# GALX4-0047N_PCB-1109N_REV-A_io_2.net
KiCad netlist of a schematic drawn in Altium Designer
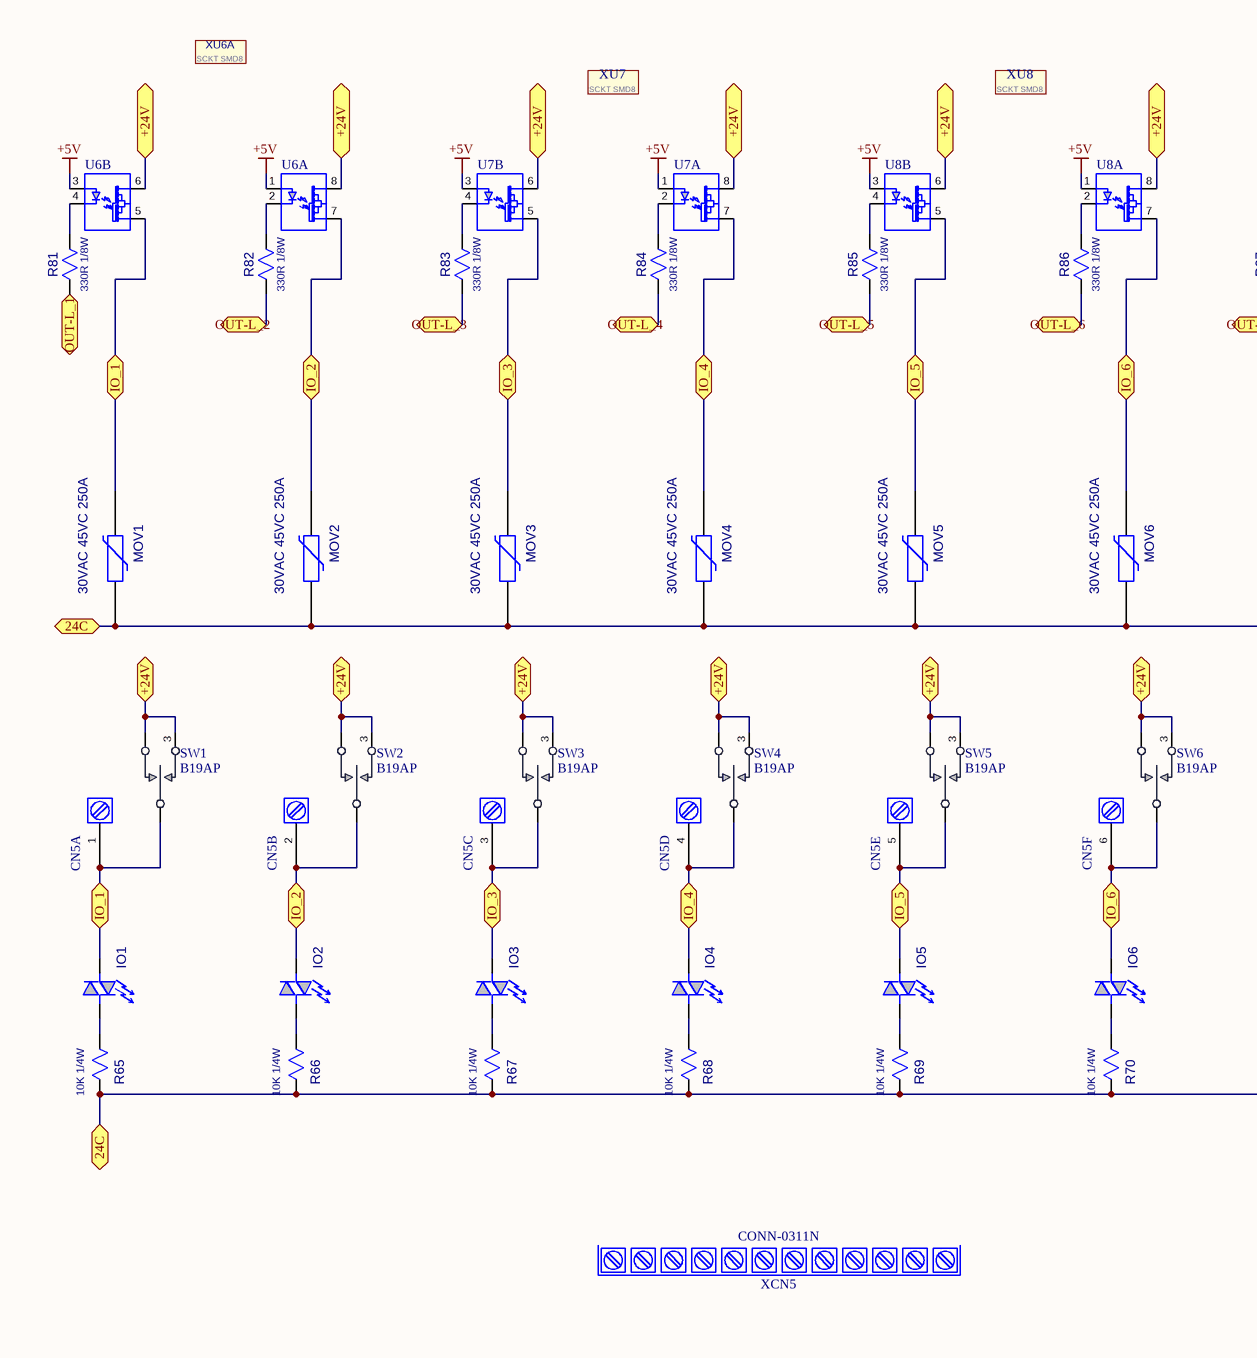
[diagram p0: GALX4-0047N_PCB-1109N_REV-A_io_2.SchDoc, left]
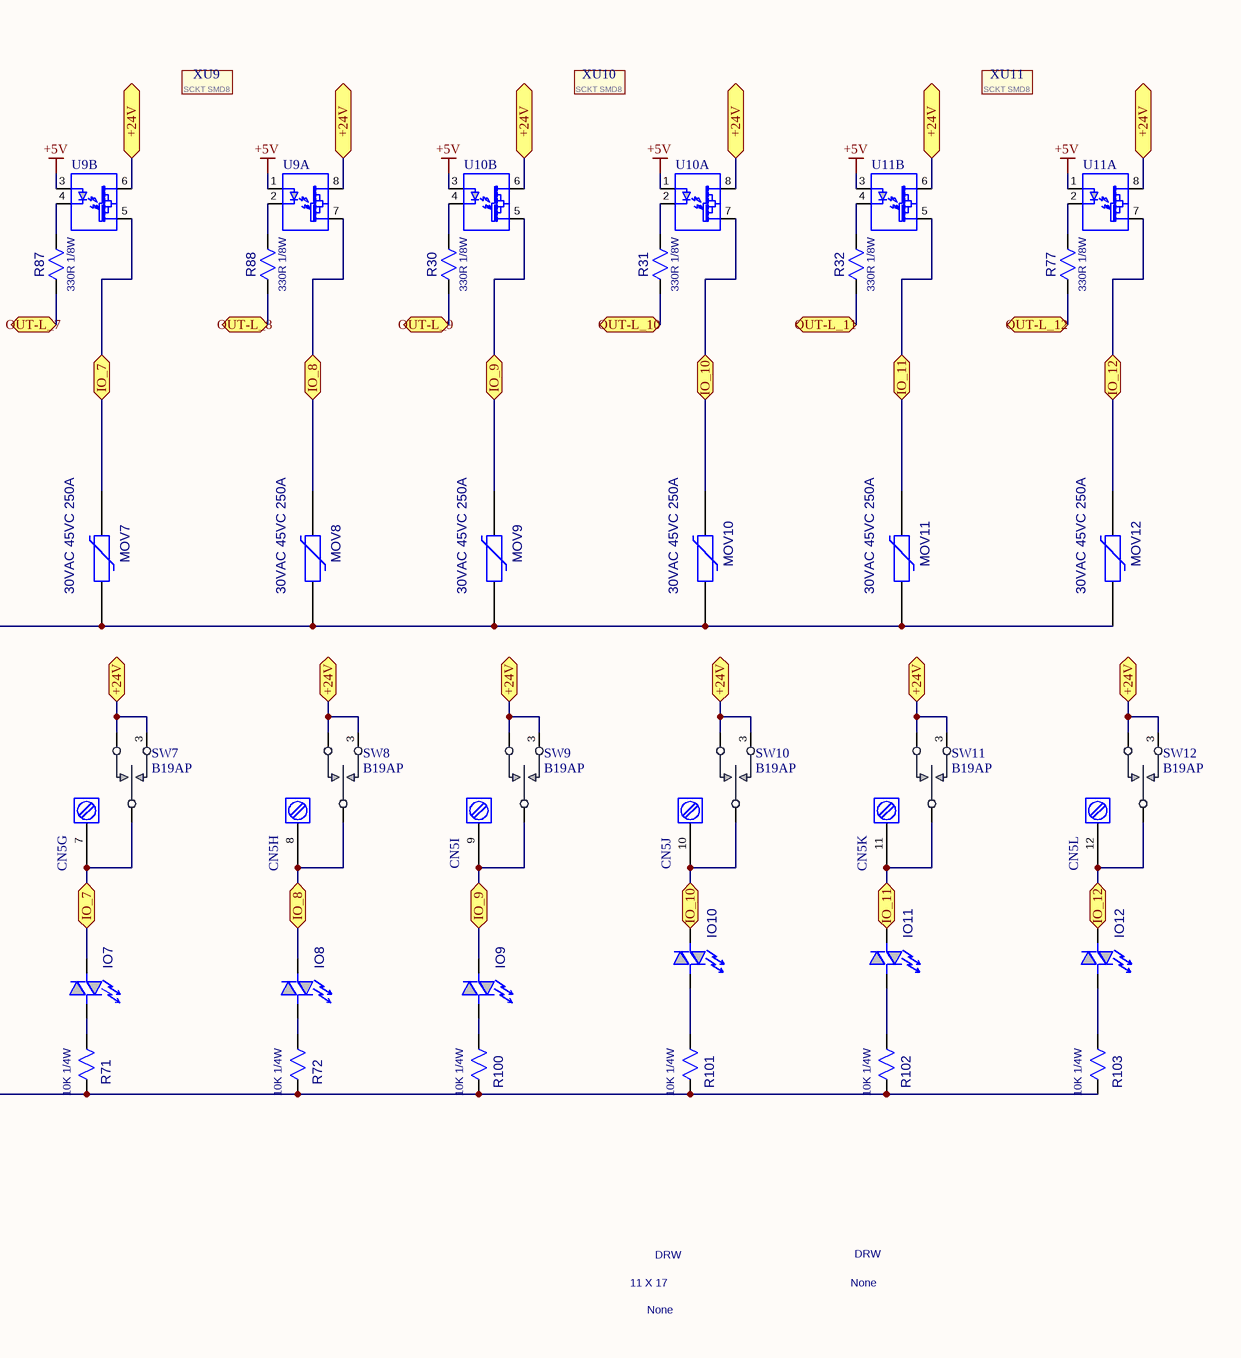
[diagram p1: GALX4-0047N_PCB-1109N_REV-A_io_2.SchDoc, right]

(export (version "E")
  (design (tool "Eeschema 10.0.6"))
  (components
    (comp (ref "CN5")
      (value "CONN-0310N")
      (footprint "CNPIN-5MM-12P-NOSCR")
      (description "CNPIN_5MM_12P")
      (fields (field (name "MANUFACTURER") "PHOENIX"))
      (libsource (lib "") (part "CONN-0310N_1"))
    )
    (comp (ref "IO1")
      (value "LED-0013N")
      (footprint "1206-LED-GREEN")
      (description "LED-1206-BI-G")
      (fields (field (name "MANUFACTURER") "SUNLED"))
      (libsource (lib "SEMICONDUCTOR") (part "LED-0013N"))
    )
    (comp (ref "IO2")
      (value "LED-0013N")
      (footprint "1206-LED-GREEN")
      (description "LED-1206-BI-G")
      (fields (field (name "MANUFACTURER") "SUNLED"))
      (libsource (lib "SEMICONDUCTOR") (part "LED-0013N"))
    )
    (comp (ref "IO3")
      (value "LED-0013N")
      (footprint "1206-LED-GREEN")
      (description "LED-1206-BI-G")
      (fields (field (name "MANUFACTURER") "SUNLED"))
      (libsource (lib "SEMICONDUCTOR") (part "LED-0013N"))
    )
    (comp (ref "IO4")
      (value "LED-0013N")
      (footprint "1206-LED-GREEN")
      (description "LED-1206-BI-G")
      (fields (field (name "MANUFACTURER") "SUNLED"))
      (libsource (lib "SEMICONDUCTOR") (part "LED-0013N"))
    )
    (comp (ref "IO5")
      (value "LED-0013N")
      (footprint "1206-LED-GREEN")
      (description "LED-1206-BI-G")
      (fields (field (name "MANUFACTURER") "SUNLED"))
      (libsource (lib "SEMICONDUCTOR") (part "LED-0013N"))
    )
    (comp (ref "IO6")
      (value "LED-0013N")
      (footprint "1206-LED-GREEN")
      (description "LED-1206-BI-G")
      (fields (field (name "MANUFACTURER") "SUNLED"))
      (libsource (lib "SEMICONDUCTOR") (part "LED-0013N"))
    )
    (comp (ref "IO7")
      (value "LED-0013N")
      (footprint "1206-LED-GREEN")
      (description "LED-1206-BI-G")
      (fields (field (name "MANUFACTURER") "SUNLED"))
      (libsource (lib "SEMICONDUCTOR") (part "LED-0013N"))
    )
    (comp (ref "IO8")
      (value "LED-0013N")
      (footprint "1206-LED-GREEN")
      (description "LED-1206-BI-G")
      (fields (field (name "MANUFACTURER") "SUNLED"))
      (libsource (lib "SEMICONDUCTOR") (part "LED-0013N"))
    )
    (comp (ref "IO9")
      (value "LED-0013N")
      (footprint "1206-LED-GREEN")
      (description "LED-1206-BI-G")
      (fields (field (name "MANUFACTURER") "SUNLED"))
      (libsource (lib "SEMICONDUCTOR") (part "LED-0013N"))
    )
    (comp (ref "IO10")
      (value "LED-0013N")
      (footprint "1206-LED-GREEN")
      (description "LED-1206-BI-G")
      (fields (field (name "MANUFACTURER") "SUNLED"))
      (libsource (lib "SEMICONDUCTOR") (part "LED-0013N"))
    )
    (comp (ref "IO11")
      (value "LED-0013N")
      (footprint "1206-LED-GREEN")
      (description "LED-1206-BI-G")
      (fields (field (name "MANUFACTURER") "SUNLED"))
      (libsource (lib "SEMICONDUCTOR") (part "LED-0013N"))
    )
    (comp (ref "IO12")
      (value "LED-0013N")
      (footprint "1206-LED-GREEN")
      (description "LED-1206-BI-G")
      (fields (field (name "MANUFACTURER") "SUNLED"))
      (libsource (lib "SEMICONDUCTOR") (part "LED-0013N"))
    )
    (comp (ref "MOV1")
      (value "30VAC 45VC 250A")
      (footprint "DISC-280DX150WX200P")
      (description "MOV-30VAC-45VC-250A-7MM-STRAIGHT")
      (fields (field (name "MANUFACTURER") "LITTLEFUSE") (field (name "Comment") "MOV-0012N"))
      (libsource (lib "SEMICONDUCTOR") (part "MOV-0012N"))
    )
    (comp (ref "MOV2")
      (value "30VAC 45VC 250A")
      (footprint "DISC-280DX150WX200P")
      (description "MOV-30VAC-45VC-250A-7MM-STRAIGHT")
      (fields (field (name "MANUFACTURER") "LITTLEFUSE") (field (name "Comment") "MOV-0012N"))
      (libsource (lib "SEMICONDUCTOR") (part "MOV-0012N"))
    )
    (comp (ref "MOV3")
      (value "30VAC 45VC 250A")
      (footprint "DISC-280DX150WX200P")
      (description "MOV-30VAC-45VC-250A-7MM-STRAIGHT")
      (fields (field (name "MANUFACTURER") "LITTLEFUSE") (field (name "Comment") "MOV-0012N"))
      (libsource (lib "SEMICONDUCTOR") (part "MOV-0012N"))
    )
    (comp (ref "MOV4")
      (value "30VAC 45VC 250A")
      (footprint "DISC-280DX150WX200P")
      (description "MOV-30VAC-45VC-250A-7MM-STRAIGHT")
      (fields (field (name "MANUFACTURER") "LITTLEFUSE") (field (name "Comment") "MOV-0012N"))
      (libsource (lib "SEMICONDUCTOR") (part "MOV-0012N"))
    )
    (comp (ref "MOV5")
      (value "30VAC 45VC 250A")
      (footprint "DISC-280DX150WX200P")
      (description "MOV-30VAC-45VC-250A-7MM-STRAIGHT")
      (fields (field (name "MANUFACTURER") "LITTLEFUSE") (field (name "Comment") "MOV-0012N"))
      (libsource (lib "SEMICONDUCTOR") (part "MOV-0012N"))
    )
    (comp (ref "MOV6")
      (value "30VAC 45VC 250A")
      (footprint "DISC-280DX150WX200P")
      (description "MOV-30VAC-45VC-250A-7MM-STRAIGHT")
      (fields (field (name "MANUFACTURER") "LITTLEFUSE") (field (name "Comment") "MOV-0012N"))
      (libsource (lib "SEMICONDUCTOR") (part "MOV-0012N"))
    )
    (comp (ref "MOV7")
      (value "30VAC 45VC 250A")
      (footprint "DISC-280DX150WX200P")
      (description "MOV-30VAC-45VC-250A-7MM-STRAIGHT")
      (fields (field (name "MANUFACTURER") "LITTLEFUSE") (field (name "Comment") "MOV-0012N"))
      (libsource (lib "SEMICONDUCTOR") (part "MOV-0012N"))
    )
    (comp (ref "MOV8")
      (value "30VAC 45VC 250A")
      (footprint "DISC-280DX150WX200P")
      (description "MOV-30VAC-45VC-250A-7MM-STRAIGHT")
      (fields (field (name "MANUFACTURER") "LITTLEFUSE") (field (name "Comment") "MOV-0012N"))
      (libsource (lib "SEMICONDUCTOR") (part "MOV-0012N"))
    )
    (comp (ref "MOV9")
      (value "30VAC 45VC 250A")
      (footprint "DISC-280DX150WX200P")
      (description "MOV-30VAC-45VC-250A-7MM-STRAIGHT")
      (fields (field (name "MANUFACTURER") "LITTLEFUSE") (field (name "Comment") "MOV-0012N"))
      (libsource (lib "SEMICONDUCTOR") (part "MOV-0012N"))
    )
    (comp (ref "MOV10")
      (value "30VAC 45VC 250A")
      (footprint "DISC-280DX150WX200P")
      (description "MOV-30VAC-45VC-250A-7MM-STRAIGHT")
      (fields (field (name "MANUFACTURER") "LITTLEFUSE") (field (name "Comment") "MOV-0012N"))
      (libsource (lib "SEMICONDUCTOR") (part "MOV-0012N"))
    )
    (comp (ref "MOV11")
      (value "30VAC 45VC 250A")
      (footprint "DISC-280DX150WX200P")
      (description "MOV-30VAC-45VC-250A-7MM-STRAIGHT")
      (fields (field (name "MANUFACTURER") "LITTLEFUSE") (field (name "Comment") "MOV-0012N"))
      (libsource (lib "SEMICONDUCTOR") (part "MOV-0012N"))
    )
    (comp (ref "MOV12")
      (value "30VAC 45VC 250A")
      (footprint "DISC-280DX150WX200P")
      (description "MOV-30VAC-45VC-250A-7MM-STRAIGHT")
      (fields (field (name "MANUFACTURER") "LITTLEFUSE") (field (name "Comment") "MOV-0012N"))
      (libsource (lib "SEMICONDUCTOR") (part "MOV-0012N"))
    )
    (comp (ref "R30")
      (value "330R 1/8W")
      (footprint "0805")
      (description "R-0805-A-330R-1/8-5%")
      (fields (field (name "MANUFACTURER") "KOA SPEER") (field (name "Comment") "RES-0291N"))
      (libsource (lib "RESISTOR") (part "RES-0291N"))
    )
    (comp (ref "R31")
      (value "330R 1/8W")
      (footprint "0805")
      (description "R-0805-A-330R-1/8-5%")
      (fields (field (name "MANUFACTURER") "KOA SPEER") (field (name "Comment") "RES-0291N"))
      (libsource (lib "RESISTOR") (part "RES-0291N"))
    )
    (comp (ref "R32")
      (value "330R 1/8W")
      (footprint "0805")
      (description "R-0805-A-330R-1/8-5%")
      (fields (field (name "MANUFACTURER") "KOA SPEER") (field (name "Comment") "RES-0291N"))
      (libsource (lib "RESISTOR") (part "RES-0291N"))
    )
    (comp (ref "R65")
      (value "10K 1/4W")
      (footprint "1206")
      (description "R-1206-B-10K-1/4-1%")
      (fields (field (name "MANUFACTURER") "VISHAY/DALE") (field (name "Comment") "RES-0294N"))
      (libsource (lib "RESISTOR") (part "RES-0294N"))
    )
    (comp (ref "R66")
      (value "10K 1/4W")
      (footprint "1206")
      (description "R-1206-B-10K-1/4-1%")
      (fields (field (name "MANUFACTURER") "VISHAY/DALE") (field (name "Comment") "RES-0294N"))
      (libsource (lib "RESISTOR") (part "RES-0294N"))
    )
    (comp (ref "R67")
      (value "10K 1/4W")
      (footprint "1206")
      (description "R-1206-B-10K-1/4-1%")
      (fields (field (name "MANUFACTURER") "VISHAY/DALE") (field (name "Comment") "RES-0294N"))
      (libsource (lib "RESISTOR") (part "RES-0294N"))
    )
    (comp (ref "R68")
      (value "10K 1/4W")
      (footprint "1206")
      (description "R-1206-B-10K-1/4-1%")
      (fields (field (name "MANUFACTURER") "VISHAY/DALE") (field (name "Comment") "RES-0294N"))
      (libsource (lib "RESISTOR") (part "RES-0294N"))
    )
    (comp (ref "R69")
      (value "10K 1/4W")
      (footprint "1206")
      (description "R-1206-B-10K-1/4-1%")
      (fields (field (name "MANUFACTURER") "VISHAY/DALE") (field (name "Comment") "RES-0294N"))
      (libsource (lib "RESISTOR") (part "RES-0294N"))
    )
    (comp (ref "R70")
      (value "10K 1/4W")
      (footprint "1206")
      (description "R-1206-B-10K-1/4-1%")
      (fields (field (name "MANUFACTURER") "VISHAY/DALE") (field (name "Comment") "RES-0294N"))
      (libsource (lib "RESISTOR") (part "RES-0294N"))
    )
    (comp (ref "R71")
      (value "10K 1/4W")
      (footprint "1206")
      (description "R-1206-B-10K-1/4-1%")
      (fields (field (name "MANUFACTURER") "VISHAY/DALE") (field (name "Comment") "RES-0294N"))
      (libsource (lib "RESISTOR") (part "RES-0294N"))
    )
    (comp (ref "R72")
      (value "10K 1/4W")
      (footprint "1206")
      (description "R-1206-B-10K-1/4-1%")
      (fields (field (name "MANUFACTURER") "VISHAY/DALE") (field (name "Comment") "RES-0294N"))
      (libsource (lib "RESISTOR") (part "RES-0294N"))
    )
    (comp (ref "R77")
      (value "330R 1/8W")
      (footprint "0805")
      (description "R-0805-A-330R-1/8-5%")
      (fields (field (name "MANUFACTURER") "KOA SPEER") (field (name "Comment") "RES-0291N"))
      (libsource (lib "RESISTOR") (part "RES-0291N"))
    )
    (comp (ref "R81")
      (value "330R 1/8W")
      (footprint "0805")
      (description "R-0805-A-330R-1/8-5%")
      (fields (field (name "MANUFACTURER") "KOA SPEER") (field (name "Comment") "RES-0291N"))
      (libsource (lib "RESISTOR") (part "RES-0291N"))
    )
    (comp (ref "R82")
      (value "330R 1/8W")
      (footprint "0805")
      (description "R-0805-A-330R-1/8-5%")
      (fields (field (name "MANUFACTURER") "KOA SPEER") (field (name "Comment") "RES-0291N"))
      (libsource (lib "RESISTOR") (part "RES-0291N"))
    )
    (comp (ref "R83")
      (value "330R 1/8W")
      (footprint "0805")
      (description "R-0805-A-330R-1/8-5%")
      (fields (field (name "MANUFACTURER") "KOA SPEER") (field (name "Comment") "RES-0291N"))
      (libsource (lib "RESISTOR") (part "RES-0291N"))
    )
    (comp (ref "R84")
      (value "330R 1/8W")
      (footprint "0805")
      (description "R-0805-A-330R-1/8-5%")
      (fields (field (name "MANUFACTURER") "KOA SPEER") (field (name "Comment") "RES-0291N"))
      (libsource (lib "RESISTOR") (part "RES-0291N"))
    )
    (comp (ref "R85")
      (value "330R 1/8W")
      (footprint "0805")
      (description "R-0805-A-330R-1/8-5%")
      (fields (field (name "MANUFACTURER") "KOA SPEER") (field (name "Comment") "RES-0291N"))
      (libsource (lib "RESISTOR") (part "RES-0291N"))
    )
    (comp (ref "R86")
      (value "330R 1/8W")
      (footprint "0805")
      (description "R-0805-A-330R-1/8-5%")
      (fields (field (name "MANUFACTURER") "KOA SPEER") (field (name "Comment") "RES-0291N"))
      (libsource (lib "RESISTOR") (part "RES-0291N"))
    )
    (comp (ref "R87")
      (value "330R 1/8W")
      (footprint "0805")
      (description "R-0805-A-330R-1/8-5%")
      (fields (field (name "MANUFACTURER") "KOA SPEER") (field (name "Comment") "RES-0291N"))
      (libsource (lib "RESISTOR") (part "RES-0291N"))
    )
    (comp (ref "R88")
      (value "330R 1/8W")
      (footprint "0805")
      (description "R-0805-A-330R-1/8-5%")
      (fields (field (name "MANUFACTURER") "KOA SPEER") (field (name "Comment") "RES-0291N"))
      (libsource (lib "RESISTOR") (part "RES-0291N"))
    )
    (comp (ref "R100")
      (value "10K 1/4W")
      (footprint "1206")
      (description "R-1206-B-10K-1/4-1%")
      (fields (field (name "MANUFACTURER") "VISHAY/DALE") (field (name "Comment") "RES-0294N"))
      (libsource (lib "RESISTOR") (part "RES-0294N"))
    )
    (comp (ref "R101")
      (value "10K 1/4W")
      (footprint "1206")
      (description "R-1206-B-10K-1/4-1%")
      (fields (field (name "MANUFACTURER") "VISHAY/DALE") (field (name "Comment") "RES-0294N"))
      (libsource (lib "RESISTOR") (part "RES-0294N"))
    )
    (comp (ref "R102")
      (value "10K 1/4W")
      (footprint "1206")
      (description "R-1206-B-10K-1/4-1%")
      (fields (field (name "MANUFACTURER") "VISHAY/DALE") (field (name "Comment") "RES-0294N"))
      (libsource (lib "RESISTOR") (part "RES-0294N"))
    )
    (comp (ref "R103")
      (value "10K 1/4W")
      (footprint "1206")
      (description "R-1206-B-10K-1/4-1%")
      (fields (field (name "MANUFACTURER") "VISHAY/DALE") (field (name "Comment") "RES-0294N"))
      (libsource (lib "RESISTOR") (part "RES-0294N"))
    )
    (comp (ref "SW1")
      (value "ON-OFF-MON")
      (footprint "B19AP")
      (description "SWITCH,MOMENTARY TOGGLE")
      (fields (field (name "MANUFACTURER") "NKK") (field (name "MFG PART ID") "B19AP"))
      (libsource (lib "My Local Library") (part "SW-0083N"))
    )
    (comp (ref "SW2")
      (value "ON-OFF-MON")
      (footprint "B19AP")
      (description "SWITCH,MOMENTARY TOGGLE")
      (fields (field (name "MANUFACTURER") "NKK") (field (name "MFG PART ID") "B19AP"))
      (libsource (lib "My Local Library") (part "SW-0083N"))
    )
    (comp (ref "SW3")
      (value "ON-OFF-MON")
      (footprint "B19AP")
      (description "SWITCH,MOMENTARY TOGGLE")
      (fields (field (name "MANUFACTURER") "NKK") (field (name "MFG PART ID") "B19AP"))
      (libsource (lib "My Local Library") (part "SW-0083N"))
    )
    (comp (ref "SW4")
      (value "ON-OFF-MON")
      (footprint "B19AP")
      (description "SWITCH,MOMENTARY TOGGLE")
      (fields (field (name "MANUFACTURER") "NKK") (field (name "MFG PART ID") "B19AP"))
      (libsource (lib "My Local Library") (part "SW-0083N"))
    )
    (comp (ref "SW5")
      (value "ON-OFF-MON")
      (footprint "B19AP")
      (description "SWITCH,MOMENTARY TOGGLE")
      (fields (field (name "MANUFACTURER") "NKK") (field (name "MFG PART ID") "B19AP"))
      (libsource (lib "My Local Library") (part "SW-0083N"))
    )
    (comp (ref "SW6")
      (value "ON-OFF-MON")
      (footprint "B19AP")
      (description "SWITCH,MOMENTARY TOGGLE")
      (fields (field (name "MANUFACTURER") "NKK") (field (name "MFG PART ID") "B19AP"))
      (libsource (lib "My Local Library") (part "SW-0083N"))
    )
    (comp (ref "SW7")
      (value "ON-OFF-MON")
      (footprint "B19AP")
      (description "SWITCH,MOMENTARY TOGGLE")
      (fields (field (name "MANUFACTURER") "NKK") (field (name "MFG PART ID") "B19AP"))
      (libsource (lib "My Local Library") (part "SW-0083N"))
    )
    (comp (ref "SW8")
      (value "ON-OFF-MON")
      (footprint "B19AP")
      (description "SWITCH,MOMENTARY TOGGLE")
      (fields (field (name "MANUFACTURER") "NKK") (field (name "MFG PART ID") "B19AP"))
      (libsource (lib "My Local Library") (part "SW-0083N"))
    )
    (comp (ref "SW9")
      (value "ON-OFF-MON")
      (footprint "B19AP")
      (description "SWITCH,MOMENTARY TOGGLE")
      (fields (field (name "MANUFACTURER") "NKK") (field (name "MFG PART ID") "B19AP"))
      (libsource (lib "My Local Library") (part "SW-0083N"))
    )
    (comp (ref "SW10")
      (value "ON-OFF-MON")
      (footprint "B19AP")
      (description "SWITCH,MOMENTARY TOGGLE")
      (fields (field (name "MANUFACTURER") "NKK") (field (name "MFG PART ID") "B19AP"))
      (libsource (lib "My Local Library") (part "SW-0083N"))
    )
    (comp (ref "SW11")
      (value "ON-OFF-MON")
      (footprint "B19AP")
      (description "SWITCH,MOMENTARY TOGGLE")
      (fields (field (name "MANUFACTURER") "NKK") (field (name "MFG PART ID") "B19AP"))
      (libsource (lib "My Local Library") (part "SW-0083N"))
    )
    (comp (ref "SW12")
      (value "ON-OFF-MON")
      (footprint "B19AP")
      (description "SWITCH,MOMENTARY TOGGLE")
      (fields (field (name "MANUFACTURER") "NKK") (field (name "MFG PART ID") "B19AP"))
      (libsource (lib "My Local Library") (part "SW-0083N"))
    )
    (comp (ref "U6")
      (value "IC-0187N")
      (footprint "DIP8FORSMD")
      (description "SSR-2CHFET-60V-0.5A-DIP8")
      (fields (field (name "MANUFACTURER") "PANASONIC"))
      (libsource (lib "IC") (part "IC-0187N"))
    )
    (comp (ref "U7")
      (value "IC-0187N")
      (footprint "DIP8FORSMD")
      (description "SSR-2CHFET-60V-0.5A-DIP8")
      (fields (field (name "MANUFACTURER") "PANASONIC"))
      (libsource (lib "IC") (part "IC-0187N"))
    )
    (comp (ref "U8")
      (value "IC-0187N")
      (footprint "DIP8FORSMD")
      (description "SSR-2CHFET-60V-0.5A-DIP8")
      (fields (field (name "MANUFACTURER") "PANASONIC"))
      (libsource (lib "IC") (part "IC-0187N"))
    )
    (comp (ref "U9")
      (value "IC-0187N")
      (footprint "DIP8FORSMD")
      (description "SSR-2CHFET-60V-0.5A-DIP8")
      (fields (field (name "MANUFACTURER") "PANASONIC"))
      (libsource (lib "IC") (part "IC-0187N"))
    )
    (comp (ref "U10")
      (value "IC-0187N")
      (footprint "DIP8FORSMD")
      (description "SSR-2CHFET-60V-0.5A-DIP8")
      (fields (field (name "MANUFACTURER") "PANASONIC"))
      (libsource (lib "IC") (part "IC-0187N"))
    )
    (comp (ref "U11")
      (value "IC-0187N")
      (footprint "DIP8FORSMD")
      (description "SSR-2CHFET-60V-0.5A-DIP8")
      (fields (field (name "MANUFACTURER") "PANASONIC"))
      (libsource (lib "IC") (part "IC-0187N"))
    )
    (comp (ref "XCN5")
      (value "CONN-0311N")
      (description "CN_5MM_12P_LABELED_PLUG(BOM)")
      (fields (field (name "MANUFACTURER") "PHOENIX") (field (name "PART TYPE") "CONN-0311N"))
      (libsource (lib "CONNECTOR") (part "CONN-0311N"))
    )
    (comp (ref "XU6A")
      (value "SCKT SMD8")
      (footprint "SCKT-SMD8")
      (description "SOCKET_SMD8")
      (fields (field (name "MANUFACTURER") "MILL-MAX") (field (name "Comment") "SCKT-0028N"))
      (libsource (lib "IC") (part "SCKT-0028N"))
    )
    (comp (ref "XU7")
      (value "SCKT SMD8")
      (footprint "SCKT-SMD8")
      (description "SOCKET_SMD8")
      (fields (field (name "MANUFACTURER") "MILL-MAX") (field (name "Comment") "SCKT-0028N"))
      (libsource (lib "IC") (part "SCKT-0028N"))
    )
    (comp (ref "XU8")
      (value "SCKT SMD8")
      (footprint "SCKT-SMD8")
      (description "SOCKET_SMD8")
      (fields (field (name "MANUFACTURER") "MILL-MAX") (field (name "Comment") "SCKT-0028N"))
      (libsource (lib "IC") (part "SCKT-0028N"))
    )
    (comp (ref "XU9")
      (value "SCKT SMD8")
      (footprint "SCKT-SMD8")
      (description "SOCKET_SMD8")
      (fields (field (name "MANUFACTURER") "MILL-MAX") (field (name "Comment") "SCKT-0028N"))
      (libsource (lib "IC") (part "SCKT-0028N"))
    )
    (comp (ref "XU10")
      (value "SCKT SMD8")
      (footprint "SCKT-SMD8")
      (description "SOCKET_SMD8")
      (fields (field (name "MANUFACTURER") "MILL-MAX") (field (name "Comment") "SCKT-0028N"))
      (libsource (lib "IC") (part "SCKT-0028N"))
    )
    (comp (ref "XU11")
      (value "SCKT SMD8")
      (footprint "SCKT-SMD8")
      (description "SOCKET_SMD8")
      (fields (field (name "MANUFACTURER") "MILL-MAX") (field (name "Comment") "SCKT-0028N"))
      (libsource (lib "IC") (part "SCKT-0028N"))
    )
  )
  (nets
    (net (code "1") (name "+5V") (class "Default")
      (node (ref "U10") (pin "1") (pintype "passive"))
      (node (ref "U10") (pin "3") (pintype "passive"))
      (node (ref "U11") (pin "1") (pintype "passive"))
      (node (ref "U11") (pin "3") (pintype "passive"))
      (node (ref "U6") (pin "1") (pintype "passive"))
      (node (ref "U6") (pin "3") (pintype "passive"))
      (node (ref "U7") (pin "1") (pintype "passive"))
      (node (ref "U7") (pin "3") (pintype "passive"))
      (node (ref "U8") (pin "1") (pintype "passive"))
      (node (ref "U8") (pin "3") (pintype "passive"))
      (node (ref "U9") (pin "1") (pintype "passive"))
      (node (ref "U9") (pin "3") (pintype "passive"))
    )
    (net (code "2") (name "/+24V") (class "Default")
      (node (ref "SW1") (pin "1") (pintype "passive"))
      (node (ref "SW1") (pin "3") (pinfunction "MON_3") (pintype "passive"))
      (node (ref "SW10") (pin "1") (pintype "passive"))
      (node (ref "SW10") (pin "3") (pinfunction "MON_3") (pintype "passive"))
      (node (ref "SW11") (pin "1") (pintype "passive"))
      (node (ref "SW11") (pin "3") (pinfunction "MON_3") (pintype "passive"))
      (node (ref "SW12") (pin "1") (pintype "passive"))
      (node (ref "SW12") (pin "3") (pinfunction "MON_3") (pintype "passive"))
      (node (ref "SW2") (pin "1") (pintype "passive"))
      (node (ref "SW2") (pin "3") (pinfunction "MON_3") (pintype "passive"))
      (node (ref "SW3") (pin "1") (pintype "passive"))
      (node (ref "SW3") (pin "3") (pinfunction "MON_3") (pintype "passive"))
      (node (ref "SW4") (pin "1") (pintype "passive"))
      (node (ref "SW4") (pin "3") (pinfunction "MON_3") (pintype "passive"))
      (node (ref "SW5") (pin "1") (pintype "passive"))
      (node (ref "SW5") (pin "3") (pinfunction "MON_3") (pintype "passive"))
      (node (ref "SW6") (pin "1") (pintype "passive"))
      (node (ref "SW6") (pin "3") (pinfunction "MON_3") (pintype "passive"))
      (node (ref "SW7") (pin "1") (pintype "passive"))
      (node (ref "SW7") (pin "3") (pinfunction "MON_3") (pintype "passive"))
      (node (ref "SW8") (pin "1") (pintype "passive"))
      (node (ref "SW8") (pin "3") (pinfunction "MON_3") (pintype "passive"))
      (node (ref "SW9") (pin "1") (pintype "passive"))
      (node (ref "SW9") (pin "3") (pinfunction "MON_3") (pintype "passive"))
      (node (ref "U10") (pin "6") (pinfunction "4_6") (pintype "passive"))
      (node (ref "U10") (pin "8") (pinfunction "8_8") (pintype "passive"))
      (node (ref "U11") (pin "6") (pinfunction "4_6") (pintype "passive"))
      (node (ref "U11") (pin "8") (pinfunction "8_8") (pintype "passive"))
      (node (ref "U6") (pin "6") (pinfunction "4_6") (pintype "passive"))
      (node (ref "U6") (pin "8") (pinfunction "8_8") (pintype "passive"))
      (node (ref "U7") (pin "6") (pinfunction "4_6") (pintype "passive"))
      (node (ref "U7") (pin "8") (pinfunction "8_8") (pintype "passive"))
      (node (ref "U8") (pin "6") (pinfunction "4_6") (pintype "passive"))
      (node (ref "U8") (pin "8") (pinfunction "8_8") (pintype "passive"))
      (node (ref "U9") (pin "6") (pinfunction "4_6") (pintype "passive"))
      (node (ref "U9") (pin "8") (pinfunction "8_8") (pintype "passive"))
    )
    (net (code "3") (name "/24C") (class "Default")
      (node (ref "MOV1") (pin "2") (pintype "passive"))
      (node (ref "MOV10") (pin "2") (pintype "passive"))
      (node (ref "MOV11") (pin "2") (pintype "passive"))
      (node (ref "MOV12") (pin "2") (pintype "passive"))
      (node (ref "MOV2") (pin "2") (pintype "passive"))
      (node (ref "MOV3") (pin "2") (pintype "passive"))
      (node (ref "MOV4") (pin "2") (pintype "passive"))
      (node (ref "MOV5") (pin "2") (pintype "passive"))
      (node (ref "MOV6") (pin "2") (pintype "passive"))
      (node (ref "MOV7") (pin "2") (pintype "passive"))
      (node (ref "MOV8") (pin "2") (pintype "passive"))
      (node (ref "MOV9") (pin "2") (pintype "passive"))
      (node (ref "R100") (pin "2") (pintype "passive"))
      (node (ref "R101") (pin "2") (pintype "passive"))
      (node (ref "R102") (pin "2") (pintype "passive"))
      (node (ref "R103") (pin "2") (pintype "passive"))
      (node (ref "R65") (pin "2") (pintype "passive"))
      (node (ref "R66") (pin "2") (pintype "passive"))
      (node (ref "R67") (pin "2") (pintype "passive"))
      (node (ref "R68") (pin "2") (pintype "passive"))
      (node (ref "R69") (pin "2") (pintype "passive"))
      (node (ref "R70") (pin "2") (pintype "passive"))
      (node (ref "R71") (pin "2") (pintype "passive"))
      (node (ref "R72") (pin "2") (pintype "passive"))
    )
    (net (code "4") (name "/IO_1") (class "Default")
      (node (ref "CN5") (pin "1") (pintype "passive"))
      (node (ref "IO1") (pin "1") (pintype "passive"))
      (node (ref "MOV1") (pin "1") (pintype "passive"))
      (node (ref "SW1") (pin "2") (pintype "passive"))
      (node (ref "U6") (pin "5") (pinfunction "5_5") (pintype "passive"))
    )
    (net (code "5") (name "/IO_2") (class "Default")
      (node (ref "CN5") (pin "2") (pintype "passive"))
      (node (ref "IO2") (pin "1") (pintype "passive"))
      (node (ref "MOV2") (pin "1") (pintype "passive"))
      (node (ref "SW2") (pin "2") (pintype "passive"))
      (node (ref "U6") (pin "7") (pinfunction "7_7") (pintype "passive"))
    )
    (net (code "6") (name "/IO_3") (class "Default")
      (node (ref "CN5") (pin "3") (pintype "passive"))
      (node (ref "IO3") (pin "1") (pintype "passive"))
      (node (ref "MOV3") (pin "1") (pintype "passive"))
      (node (ref "SW3") (pin "2") (pintype "passive"))
      (node (ref "U7") (pin "5") (pinfunction "5_5") (pintype "passive"))
    )
    (net (code "7") (name "/IO_4") (class "Default")
      (node (ref "CN5") (pin "4") (pintype "passive"))
      (node (ref "IO4") (pin "1") (pintype "passive"))
      (node (ref "MOV4") (pin "1") (pintype "passive"))
      (node (ref "SW4") (pin "2") (pintype "passive"))
      (node (ref "U7") (pin "7") (pinfunction "7_7") (pintype "passive"))
    )
    (net (code "8") (name "/IO_5") (class "Default")
      (node (ref "CN5") (pin "5") (pintype "passive"))
      (node (ref "IO5") (pin "1") (pintype "passive"))
      (node (ref "MOV5") (pin "1") (pintype "passive"))
      (node (ref "SW5") (pin "2") (pintype "passive"))
      (node (ref "U8") (pin "5") (pinfunction "5_5") (pintype "passive"))
    )
    (net (code "9") (name "/IO_6") (class "Default")
      (node (ref "CN5") (pin "6") (pintype "passive"))
      (node (ref "IO6") (pin "1") (pintype "passive"))
      (node (ref "MOV6") (pin "1") (pintype "passive"))
      (node (ref "SW6") (pin "2") (pintype "passive"))
      (node (ref "U8") (pin "7") (pinfunction "7_7") (pintype "passive"))
    )
    (net (code "10") (name "/IO_7") (class "Default")
      (node (ref "CN5") (pin "7") (pintype "passive"))
      (node (ref "IO7") (pin "1") (pintype "passive"))
      (node (ref "MOV7") (pin "1") (pintype "passive"))
      (node (ref "SW7") (pin "2") (pintype "passive"))
      (node (ref "U9") (pin "5") (pinfunction "5_5") (pintype "passive"))
    )
    (net (code "11") (name "/IO_8") (class "Default")
      (node (ref "CN5") (pin "8") (pintype "passive"))
      (node (ref "IO8") (pin "1") (pintype "passive"))
      (node (ref "MOV8") (pin "1") (pintype "passive"))
      (node (ref "SW8") (pin "2") (pintype "passive"))
      (node (ref "U9") (pin "7") (pinfunction "7_7") (pintype "passive"))
    )
    (net (code "12") (name "/IO_9") (class "Default")
      (node (ref "CN5") (pin "9") (pintype "passive"))
      (node (ref "IO9") (pin "1") (pintype "passive"))
      (node (ref "MOV9") (pin "1") (pintype "passive"))
      (node (ref "SW9") (pin "2") (pintype "passive"))
      (node (ref "U10") (pin "5") (pinfunction "5_5") (pintype "passive"))
    )
    (net (code "13") (name "/IO_10") (class "Default")
      (node (ref "CN5") (pin "10") (pintype "passive"))
      (node (ref "IO10") (pin "1") (pintype "passive"))
      (node (ref "MOV10") (pin "1") (pintype "passive"))
      (node (ref "SW10") (pin "2") (pintype "passive"))
      (node (ref "U10") (pin "7") (pinfunction "7_7") (pintype "passive"))
    )
    (net (code "14") (name "/IO_11") (class "Default")
      (node (ref "CN5") (pin "11") (pintype "passive"))
      (node (ref "IO11") (pin "1") (pintype "passive"))
      (node (ref "MOV11") (pin "1") (pintype "passive"))
      (node (ref "SW11") (pin "2") (pintype "passive"))
      (node (ref "U11") (pin "5") (pinfunction "5_5") (pintype "passive"))
    )
    (net (code "15") (name "/IO_12") (class "Default")
      (node (ref "CN5") (pin "12") (pintype "passive"))
      (node (ref "IO12") (pin "1") (pintype "passive"))
      (node (ref "MOV12") (pin "1") (pintype "passive"))
      (node (ref "SW12") (pin "2") (pintype "passive"))
      (node (ref "U11") (pin "7") (pinfunction "7_7") (pintype "passive"))
    )
    (net (code "16") (name "/OUT-L_1") (class "Default") (node (ref "R81") (pin "1") (pintype "passive")))
    (net (code "17") (name "/OUT-L_2") (class "Default") (node (ref "R82") (pin "1") (pintype "passive")))
    (net (code "18") (name "/OUT-L_3") (class "Default") (node (ref "R83") (pin "1") (pintype "passive")))
    (net (code "19") (name "/OUT-L_4") (class "Default") (node (ref "R84") (pin "1") (pintype "passive")))
    (net (code "20") (name "/OUT-L_5") (class "Default") (node (ref "R85") (pin "1") (pintype "passive")))
    (net (code "21") (name "/OUT-L_6") (class "Default") (node (ref "R86") (pin "1") (pintype "passive")))
    (net (code "22") (name "/OUT-L_7") (class "Default") (node (ref "R87") (pin "1") (pintype "passive")))
    (net (code "23") (name "/OUT-L_8") (class "Default") (node (ref "R88") (pin "1") (pintype "passive")))
    (net (code "24") (name "/OUT-L_9") (class "Default") (node (ref "R30") (pin "1") (pintype "passive")))
    (net (code "25") (name "/OUT-L_10") (class "Default") (node (ref "R31") (pin "1") (pintype "passive")))
    (net (code "26") (name "/OUT-L_11") (class "Default") (node (ref "R32") (pin "1") (pintype "passive")))
    (net (code "27") (name "/OUT-L_12") (class "Default") (node (ref "R77") (pin "1") (pintype "passive")))
    (net (code "28") (name "Net-(IO1-Pad2)") (class "Default")
      (node (ref "IO1") (pin "2") (pintype "passive"))
      (node (ref "R65") (pin "1") (pintype "passive"))
    )
    (net (code "29") (name "Net-(IO2-Pad2)") (class "Default")
      (node (ref "IO2") (pin "2") (pintype "passive"))
      (node (ref "R66") (pin "1") (pintype "passive"))
    )
    (net (code "30") (name "Net-(IO3-Pad2)") (class "Default")
      (node (ref "IO3") (pin "2") (pintype "passive"))
      (node (ref "R67") (pin "1") (pintype "passive"))
    )
    (net (code "31") (name "Net-(IO4-Pad2)") (class "Default")
      (node (ref "IO4") (pin "2") (pintype "passive"))
      (node (ref "R68") (pin "1") (pintype "passive"))
    )
    (net (code "32") (name "Net-(IO5-Pad2)") (class "Default")
      (node (ref "IO5") (pin "2") (pintype "passive"))
      (node (ref "R69") (pin "1") (pintype "passive"))
    )
    (net (code "33") (name "Net-(IO6-Pad2)") (class "Default")
      (node (ref "IO6") (pin "2") (pintype "passive"))
      (node (ref "R70") (pin "1") (pintype "passive"))
    )
    (net (code "34") (name "Net-(IO7-Pad2)") (class "Default")
      (node (ref "IO7") (pin "2") (pintype "passive"))
      (node (ref "R71") (pin "1") (pintype "passive"))
    )
    (net (code "35") (name "Net-(IO8-Pad2)") (class "Default")
      (node (ref "IO8") (pin "2") (pintype "passive"))
      (node (ref "R72") (pin "1") (pintype "passive"))
    )
    (net (code "36") (name "Net-(IO9-Pad2)") (class "Default")
      (node (ref "IO9") (pin "2") (pintype "passive"))
      (node (ref "R100") (pin "1") (pintype "passive"))
    )
    (net (code "37") (name "Net-(IO10-Pad2)") (class "Default")
      (node (ref "IO10") (pin "2") (pintype "passive"))
      (node (ref "R101") (pin "1") (pintype "passive"))
    )
    (net (code "38") (name "Net-(IO11-Pad2)") (class "Default")
      (node (ref "IO11") (pin "2") (pintype "passive"))
      (node (ref "R102") (pin "1") (pintype "passive"))
    )
    (net (code "39") (name "Net-(IO12-Pad2)") (class "Default")
      (node (ref "IO12") (pin "2") (pintype "passive"))
      (node (ref "R103") (pin "1") (pintype "passive"))
    )
    (net (code "40") (name "Net-(R30-Pad2)") (class "Default")
      (node (ref "R30") (pin "2") (pintype "passive"))
      (node (ref "U10") (pin "4") (pintype "passive"))
    )
    (net (code "41") (name "Net-(R31-Pad2)") (class "Default")
      (node (ref "R31") (pin "2") (pintype "passive"))
      (node (ref "U10") (pin "2") (pintype "passive"))
    )
    (net (code "42") (name "Net-(R32-Pad2)") (class "Default")
      (node (ref "R32") (pin "2") (pintype "passive"))
      (node (ref "U11") (pin "4") (pintype "passive"))
    )
    (net (code "43") (name "Net-(R77-Pad2)") (class "Default")
      (node (ref "R77") (pin "2") (pintype "passive"))
      (node (ref "U11") (pin "2") (pintype "passive"))
    )
    (net (code "44") (name "Net-(R81-Pad2)") (class "Default")
      (node (ref "R81") (pin "2") (pintype "passive"))
      (node (ref "U6") (pin "4") (pintype "passive"))
    )
    (net (code "45") (name "Net-(R82-Pad2)") (class "Default")
      (node (ref "R82") (pin "2") (pintype "passive"))
      (node (ref "U6") (pin "2") (pintype "passive"))
    )
    (net (code "46") (name "Net-(R83-Pad2)") (class "Default")
      (node (ref "R83") (pin "2") (pintype "passive"))
      (node (ref "U7") (pin "4") (pintype "passive"))
    )
    (net (code "47") (name "Net-(R84-Pad2)") (class "Default")
      (node (ref "R84") (pin "2") (pintype "passive"))
      (node (ref "U7") (pin "2") (pintype "passive"))
    )
    (net (code "48") (name "Net-(R85-Pad2)") (class "Default")
      (node (ref "R85") (pin "2") (pintype "passive"))
      (node (ref "U8") (pin "4") (pintype "passive"))
    )
    (net (code "49") (name "Net-(R86-Pad2)") (class "Default")
      (node (ref "R86") (pin "2") (pintype "passive"))
      (node (ref "U8") (pin "2") (pintype "passive"))
    )
    (net (code "50") (name "Net-(R87-Pad2)") (class "Default")
      (node (ref "R87") (pin "2") (pintype "passive"))
      (node (ref "U9") (pin "4") (pintype "passive"))
    )
    (net (code "51") (name "Net-(R88-Pad2)") (class "Default")
      (node (ref "R88") (pin "2") (pintype "passive"))
      (node (ref "U9") (pin "2") (pintype "passive"))
    )
  )
)
